# 10-CELLULAR_COMM.net
KiCad netlist of a schematic drawn in Altium Designer
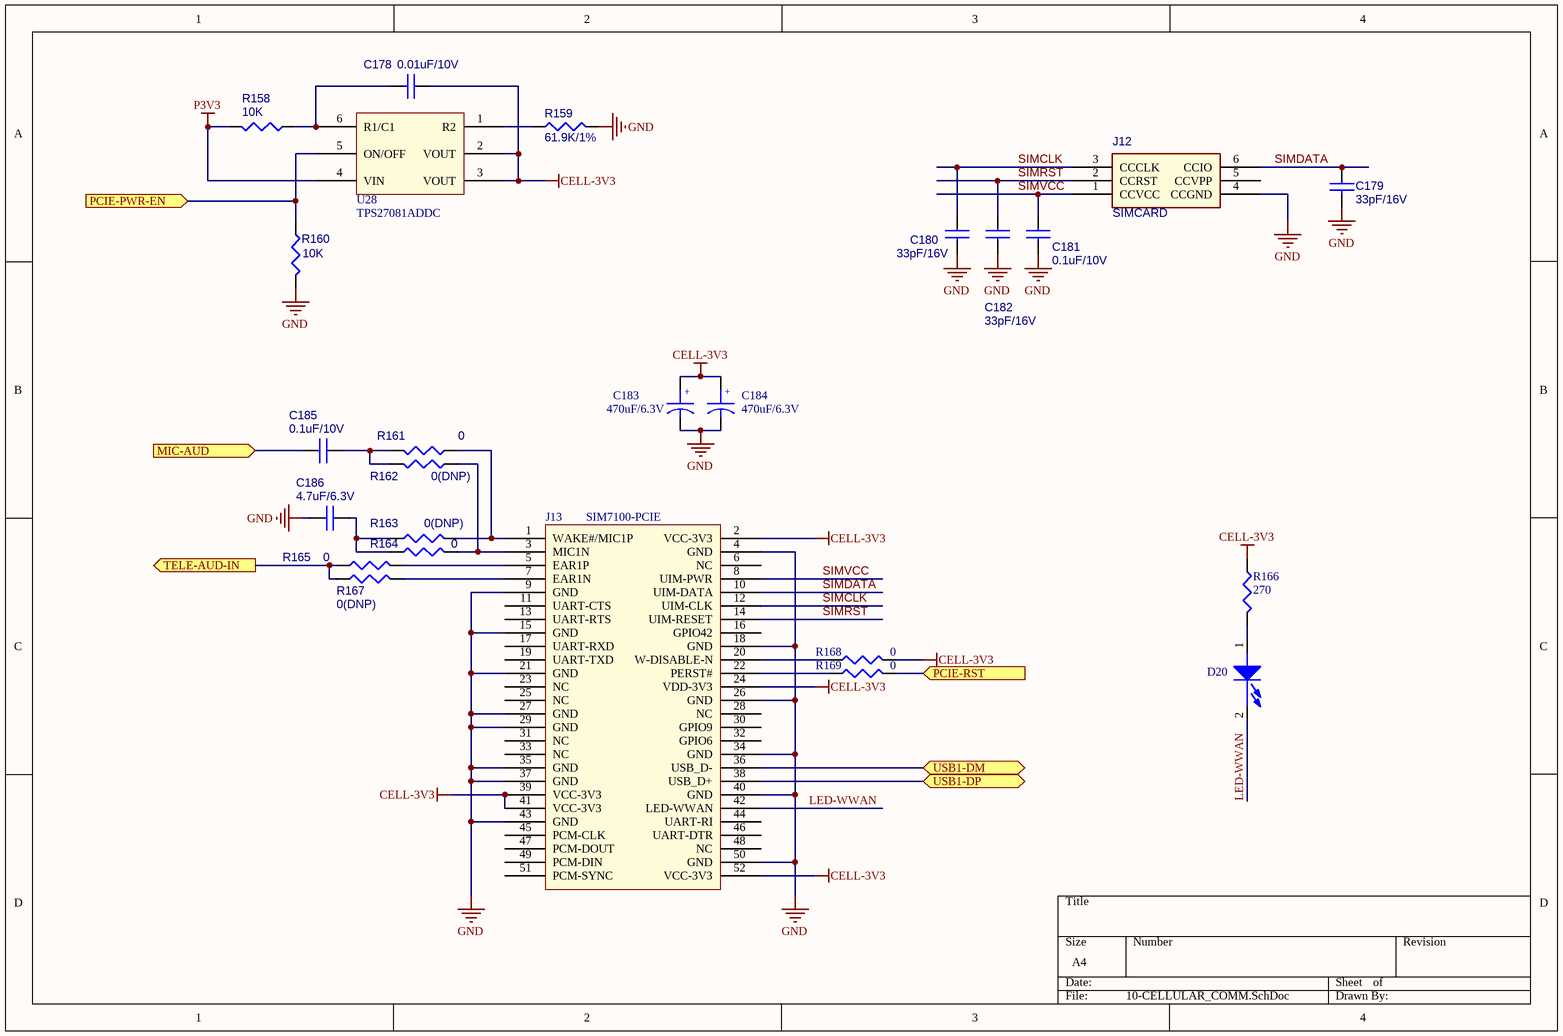
[diagram p0: 10-CELLULAR_COMM.SchDoc]

(export (version "E")
  (design (tool "Eeschema 10.0.6"))
  (components
    (comp (ref "C178") (value "0.01uF/10V") (footprint "0402") (libsource (lib "*") (part "P_CAP NP")))
    (comp (ref "C179") (value "33pF/16V") (libsource (lib "*") (part "P_CAP NP")))
    (comp (ref "C180") (value "33pF/16V") (libsource (lib "*") (part "P_CAP NP")))
    (comp (ref "C181") (value "0.1uF/10V") (libsource (lib "*") (part "P_CAP NP")))
    (comp (ref "C182") (value "33pF/16V") (libsource (lib "*") (part "P_CAP NP")))
    (comp (ref "C183") (value "470uF/6.3V") (libsource (lib "*") (part "CAP WP")))
    (comp (ref "C184") (value "470uF/6.3V") (libsource (lib "*") (part "CAP WP")))
    (comp (ref "C185") (value "0.1uF/10V") (footprint "0402") (libsource (lib "*") (part "P_CAP NP")))
    (comp (ref "C186") (value "4.7uF/6.3V") (footprint "0603") (libsource (lib "*") (part "P_CAP NP")))
    (comp (ref "D20") (value "LED GREEN") (footprint "LED0603") (libsource (lib "*") (part "LN01401_1")))
    (comp (ref "J12") (value "SIMCARD") (footprint "SIMLOCK") (libsource (lib "*") (part "SIMCARD")))
    (comp (ref "J13")
      (value "SIM7100-PCIE")
      (footprint "MINI-PCIE")
      (libsource (lib "Schlib") (part "SIM7100-PCIE"))
    )
    (comp (ref "R158") (value "10K") (footprint "0402") (libsource (lib "*") (part "P_R")))
    (comp (ref "R159") (value "61.9K/1%") (footprint "0402") (libsource (lib "*") (part "P_R")))
    (comp (ref "R160") (value "10K") (footprint "0402") (libsource (lib "*") (part "P_R")))
    (comp (ref "R161") (value "0") (footprint "0402") (libsource (lib "*") (part "P_R")))
    (comp (ref "R162") (value "0(DNP)") (footprint "0402") (libsource (lib "*") (part "P_R")))
    (comp (ref "R163") (value "0(DNP)") (footprint "0402") (libsource (lib "*") (part "P_R")))
    (comp (ref "R164") (value "0") (footprint "0402") (libsource (lib "*") (part "P_R")))
    (comp (ref "R165") (value "0") (footprint "0402") (libsource (lib "*") (part "P_R")))
    (comp (ref "R166") (value "270") (footprint "0402") (libsource (lib "*") (part "CR16-1003FM")))
    (comp (ref "R167") (value "0(DNP)") (footprint "0402") (libsource (lib "*") (part "P_R")))
    (comp (ref "R168") (value "0") (footprint "0402") (libsource (lib "*") (part "CR16-1003FM")))
    (comp (ref "R169") (value "0") (footprint "0402") (libsource (lib "*") (part "CR16-1003FM")))
    (comp (ref "U28")
      (value "TPS27081ADDC")
      (footprint "SOT23-6")
      (libsource (lib "Schlib") (part "TPS27081A"))
    )
  )
  (nets
    (net (code "1") (name "/LED-WWAN") (class "Default")
      (node (ref "D20") (pin "2") (pinfunction "CATHODE_2") (pintype "passive"))
      (node (ref "J13") (pin "42") (pinfunction "LED-WWAN_42") (pintype "passive"))
    )
    (net (code "2") (name "/MIC-AUD") (class "Default")
      (node (ref "C185") (pin "2") (pinfunction "2_2") (pintype "passive"))
    )
    (net (code "3") (name "/PCIE-PWR-EN") (class "Default")
      (node (ref "R160") (pin "2") (pinfunction "2_2") (pintype "passive"))
      (node (ref "U28") (pin "5") (pinfunction "ON/OFF_5") (pintype "passive"))
    )
    (net (code "4") (name "/PCIE-RST") (class "Default")
      (node (ref "R169") (pin "2") (pinfunction "2_2") (pintype "passive"))
    )
    (net (code "5") (name "/SIMCLK") (class "Default")
      (node (ref "C180") (pin "1") (pinfunction "1_1") (pintype "passive"))
      (node (ref "J12") (pin "3") (pinfunction "CCCLK_3") (pintype "passive"))
      (node (ref "J13") (pin "12") (pinfunction "UIM-CLK_12") (pintype "passive"))
    )
    (net (code "6") (name "/SIMDATA") (class "Default")
      (node (ref "C179") (pin "1") (pinfunction "1_1") (pintype "passive"))
      (node (ref "J12") (pin "6") (pinfunction "CCIO_6") (pintype "passive"))
      (node (ref "J13") (pin "10") (pinfunction "UIM-DATA_10") (pintype "passive"))
    )
    (net (code "7") (name "/SIMRST") (class "Default")
      (node (ref "C182") (pin "1") (pinfunction "1_1") (pintype "passive"))
      (node (ref "J12") (pin "2") (pinfunction "CCRST_2") (pintype "passive"))
      (node (ref "J13") (pin "14") (pinfunction "UIM-RESET_14") (pintype "passive"))
    )
    (net (code "8") (name "/SIMVCC") (class "Default")
      (node (ref "C181") (pin "1") (pinfunction "1_1") (pintype "passive"))
      (node (ref "J12") (pin "1") (pinfunction "CCVCC_1") (pintype "passive"))
      (node (ref "J13") (pin "8") (pinfunction "UIM-PWR_8") (pintype "passive"))
    )
    (net (code "9") (name "/TELE-AUD-IN") (class "Default")
      (node (ref "R165") (pin "2") (pinfunction "2_2") (pintype "passive"))
      (node (ref "R167") (pin "2") (pinfunction "2_2") (pintype "passive"))
    )
    (net (code "10") (name "/USB1-DM") (class "Default")
      (node (ref "J13") (pin "36") (pinfunction "USB_D-_36") (pintype "passive"))
    )
    (net (code "11") (name "/USB1-DP") (class "Default")
      (node (ref "J13") (pin "38") (pinfunction "USB_D+_38") (pintype "passive"))
    )
    (net (code "12") (name "CELL-3V3") (class "Default")
      (node (ref "C178") (pin "1") (pinfunction "1_1") (pintype "passive"))
      (node (ref "C183") (pin "1") (pinfunction "1_1") (pintype "passive"))
      (node (ref "C184") (pin "1") (pinfunction "1_1") (pintype "passive"))
      (node (ref "J13") (pin "2") (pinfunction "VCC-3V3_2") (pintype "passive"))
      (node (ref "J13") (pin "24") (pinfunction "VDD-3V3_24") (pintype "passive"))
      (node (ref "J13") (pin "39") (pinfunction "VCC-3V3_39") (pintype "passive"))
      (node (ref "J13") (pin "41") (pinfunction "VCC-3V3_41") (pintype "passive"))
      (node (ref "J13") (pin "52") (pinfunction "VCC-3V3_52") (pintype "passive"))
      (node (ref "R166") (pin "1") (pinfunction "1_1") (pintype "passive"))
      (node (ref "R168") (pin "2") (pinfunction "2_2") (pintype "passive"))
      (node (ref "U28") (pin "2") (pinfunction "VOUT_2") (pintype "passive"))
      (node (ref "U28") (pin "3") (pinfunction "VOUT_3") (pintype "passive"))
    )
    (net (code "13") (name "GND") (class "Default")
      (node (ref "C179") (pin "2") (pinfunction "2_2") (pintype "passive"))
      (node (ref "C180") (pin "2") (pinfunction "2_2") (pintype "passive"))
      (node (ref "C181") (pin "2") (pinfunction "2_2") (pintype "passive"))
      (node (ref "C182") (pin "2") (pinfunction "2_2") (pintype "passive"))
      (node (ref "C183") (pin "2") (pinfunction "2_2") (pintype "passive"))
      (node (ref "C184") (pin "2") (pinfunction "2_2") (pintype "passive"))
      (node (ref "C186") (pin "2") (pinfunction "2_2") (pintype "passive"))
      (node (ref "J12") (pin "4") (pinfunction "CCGND_4") (pintype "passive"))
      (node (ref "J13") (pin "15") (pinfunction "GND_15") (pintype "passive"))
      (node (ref "J13") (pin "18") (pinfunction "GND_18") (pintype "passive"))
      (node (ref "J13") (pin "21") (pinfunction "GND_21") (pintype "passive"))
      (node (ref "J13") (pin "26") (pinfunction "GND_26") (pintype "passive"))
      (node (ref "J13") (pin "27") (pinfunction "GND_27") (pintype "passive"))
      (node (ref "J13") (pin "29") (pinfunction "GND_29") (pintype "passive"))
      (node (ref "J13") (pin "34") (pinfunction "GND_34") (pintype "passive"))
      (node (ref "J13") (pin "35") (pinfunction "GND_35") (pintype "passive"))
      (node (ref "J13") (pin "37") (pinfunction "GND_37") (pintype "passive"))
      (node (ref "J13") (pin "4") (pinfunction "GND_4") (pintype "passive"))
      (node (ref "J13") (pin "40") (pinfunction "GND_40") (pintype "passive"))
      (node (ref "J13") (pin "43") (pinfunction "GND_43") (pintype "passive"))
      (node (ref "J13") (pin "50") (pinfunction "GND_50") (pintype "passive"))
      (node (ref "J13") (pin "9") (pinfunction "GND_9") (pintype "passive"))
      (node (ref "R159") (pin "1") (pinfunction "1_1") (pintype "passive"))
      (node (ref "R160") (pin "1") (pinfunction "1_1") (pintype "passive"))
    )
    (net (code "14") (name "Net-(C185-Pad1)") (class "Default")
      (node (ref "C185") (pin "1") (pinfunction "1_1") (pintype "passive"))
      (node (ref "R161") (pin "1") (pinfunction "1_1") (pintype "passive"))
      (node (ref "R162") (pin "1") (pinfunction "1_1") (pintype "passive"))
    )
    (net (code "15") (name "Net-(C186-Pad1)") (class "Default")
      (node (ref "C186") (pin "1") (pinfunction "1_1") (pintype "passive"))
      (node (ref "R163") (pin "2") (pinfunction "2_2") (pintype "passive"))
      (node (ref "R164") (pin "2") (pinfunction "2_2") (pintype "passive"))
    )
    (net (code "16") (name "Net-(D20-ANODE)") (class "Default")
      (node (ref "D20") (pin "1") (pinfunction "ANODE_1") (pintype "passive"))
      (node (ref "R166") (pin "2") (pinfunction "2_2") (pintype "passive"))
    )
    (net (code "17") (name "Net-(J13-EAR1N)") (class "Default")
      (node (ref "J13") (pin "7") (pinfunction "EAR1N_7") (pintype "passive"))
      (node (ref "R167") (pin "1") (pinfunction "1_1") (pintype "passive"))
    )
    (net (code "18") (name "Net-(J13-EAR1P)") (class "Default")
      (node (ref "J13") (pin "5") (pinfunction "EAR1P_5") (pintype "passive"))
      (node (ref "R165") (pin "1") (pinfunction "1_1") (pintype "passive"))
    )
    (net (code "19") (name "Net-(J13-MIC1N)") (class "Default")
      (node (ref "J13") (pin "3") (pinfunction "MIC1N_3") (pintype "passive"))
      (node (ref "R162") (pin "2") (pinfunction "2_2") (pintype "passive"))
      (node (ref "R164") (pin "1") (pinfunction "1_1") (pintype "passive"))
    )
    (net (code "20") (name "Net-(J13-PERST#)") (class "Default")
      (node (ref "J13") (pin "22") (pinfunction "PERST#_22") (pintype "passive"))
      (node (ref "R169") (pin "1") (pinfunction "1_1") (pintype "passive"))
    )
    (net (code "21") (name "Net-(J13-W-DISABLE-N)") (class "Default")
      (node (ref "J13") (pin "20") (pinfunction "W-DISABLE-N_20") (pintype "passive"))
      (node (ref "R168") (pin "1") (pinfunction "1_1") (pintype "passive"))
    )
    (net (code "22") (name "Net-(J13-WAKE#{slash}MIC1P)") (class "Default")
      (node (ref "J13") (pin "1") (pinfunction "WAKE#/MIC1P_1") (pintype "passive"))
      (node (ref "R161") (pin "2") (pinfunction "2_2") (pintype "passive"))
      (node (ref "R163") (pin "1") (pinfunction "1_1") (pintype "passive"))
    )
    (net (code "23") (name "Net-(U28-R1{slash}C1)") (class "Default")
      (node (ref "C178") (pin "2") (pinfunction "2_2") (pintype "passive"))
      (node (ref "R158") (pin "2") (pinfunction "2_2") (pintype "passive"))
      (node (ref "U28") (pin "6") (pinfunction "R1/C1_6") (pintype "passive"))
    )
    (net (code "24") (name "Net-(U28-R2)") (class "Default")
      (node (ref "R159") (pin "2") (pinfunction "2_2") (pintype "passive"))
      (node (ref "U28") (pin "1") (pinfunction "R2_1") (pintype "passive"))
    )
    (net (code "25") (name "P3V3") (class "Default")
      (node (ref "R158") (pin "1") (pinfunction "1_1") (pintype "passive"))
      (node (ref "U28") (pin "4") (pinfunction "VIN_4") (pintype "passive"))
    )
    (net (code "26") (name "unconnected-(J12-CCVPP-Pad5)") (class "Default")
      (node (ref "J12") (pin "5") (pinfunction "CCVPP_5") (pintype "passive"))
    )
    (net (code "27") (name "unconnected-(J13-GPIO6-Pad32)") (class "Default")
      (node (ref "J13") (pin "32") (pinfunction "GPIO6_32") (pintype "passive"))
    )
    (net (code "28") (name "unconnected-(J13-GPIO9-Pad30)") (class "Default")
      (node (ref "J13") (pin "30") (pinfunction "GPIO9_30") (pintype "passive"))
    )
    (net (code "29") (name "unconnected-(J13-GPIO42-Pad16)") (class "Default")
      (node (ref "J13") (pin "16") (pinfunction "GPIO42_16") (pintype "passive"))
    )
    (net (code "30") (name "unconnected-(J13-NC-Pad6)") (class "Default")
      (node (ref "J13") (pin "6") (pinfunction "NC_6") (pintype "passive"))
    )
    (net (code "31") (name "unconnected-(J13-NC-Pad23)") (class "Default")
      (node (ref "J13") (pin "23") (pinfunction "NC_23") (pintype "passive"))
    )
    (net (code "32") (name "unconnected-(J13-NC-Pad25)") (class "Default")
      (node (ref "J13") (pin "25") (pinfunction "NC_25") (pintype "passive"))
    )
    (net (code "33") (name "unconnected-(J13-NC-Pad28)") (class "Default")
      (node (ref "J13") (pin "28") (pinfunction "NC_28") (pintype "passive"))
    )
    (net (code "34") (name "unconnected-(J13-NC-Pad31)") (class "Default")
      (node (ref "J13") (pin "31") (pinfunction "NC_31") (pintype "passive"))
    )
    (net (code "35") (name "unconnected-(J13-NC-Pad33)") (class "Default")
      (node (ref "J13") (pin "33") (pinfunction "NC_33") (pintype "passive"))
    )
    (net (code "36") (name "unconnected-(J13-NC-Pad48)") (class "Default")
      (node (ref "J13") (pin "48") (pinfunction "NC_48") (pintype "passive"))
    )
    (net (code "37") (name "unconnected-(J13-PCM-CLK-Pad45)") (class "Default")
      (node (ref "J13") (pin "45") (pinfunction "PCM-CLK_45") (pintype "passive"))
    )
    (net (code "38") (name "unconnected-(J13-PCM-DIN-Pad49)") (class "Default")
      (node (ref "J13") (pin "49") (pinfunction "PCM-DIN_49") (pintype "passive"))
    )
    (net (code "39") (name "unconnected-(J13-PCM-DOUT-Pad47)") (class "Default")
      (node (ref "J13") (pin "47") (pinfunction "PCM-DOUT_47") (pintype "passive"))
    )
    (net (code "40") (name "unconnected-(J13-PCM-SYNC-Pad51)") (class "Default")
      (node (ref "J13") (pin "51") (pinfunction "PCM-SYNC_51") (pintype "passive"))
    )
    (net (code "41") (name "unconnected-(J13-UART-CTS-Pad11)") (class "Default")
      (node (ref "J13") (pin "11") (pinfunction "UART-CTS_11") (pintype "passive"))
    )
    (net (code "42") (name "unconnected-(J13-UART-DTR-Pad46)") (class "Default")
      (node (ref "J13") (pin "46") (pinfunction "UART-DTR_46") (pintype "passive"))
    )
    (net (code "43") (name "unconnected-(J13-UART-RI-Pad44)") (class "Default")
      (node (ref "J13") (pin "44") (pinfunction "UART-RI_44") (pintype "passive"))
    )
    (net (code "44") (name "unconnected-(J13-UART-RTS-Pad13)") (class "Default")
      (node (ref "J13") (pin "13") (pinfunction "UART-RTS_13") (pintype "passive"))
    )
    (net (code "45") (name "unconnected-(J13-UART-RXD-Pad17)") (class "Default")
      (node (ref "J13") (pin "17") (pinfunction "UART-RXD_17") (pintype "passive"))
    )
    (net (code "46") (name "unconnected-(J13-UART-TXD-Pad19)") (class "Default")
      (node (ref "J13") (pin "19") (pinfunction "UART-TXD_19") (pintype "passive"))
    )
  )
)
